# Membrane_Keypad.net
KiCad netlist of a schematic drawn in Altium Designer
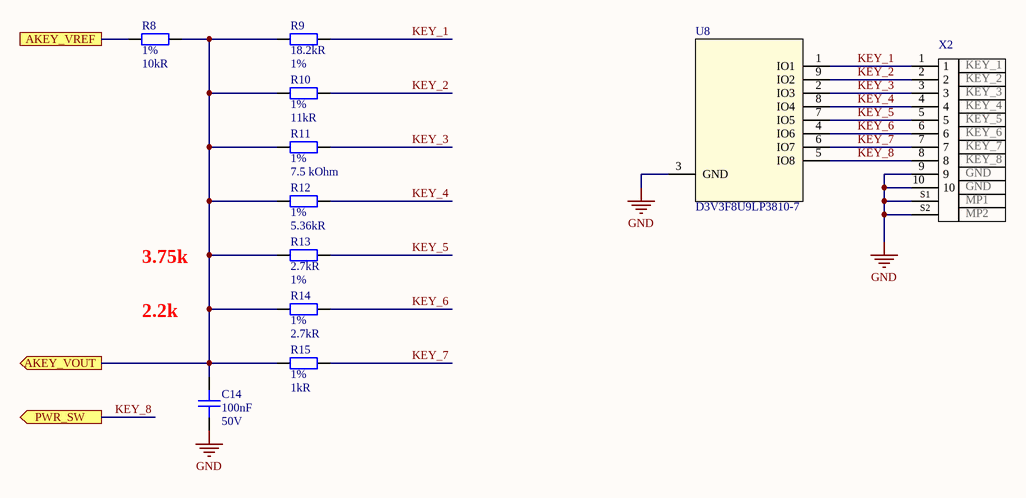
[diagram p0: Membrane_Keypad.SchDoc]

(export (version "E")
  (design (tool "Eeschema 10.0.6"))
  (components
    (comp (ref "C14")
      (value "CAP CER 0.1UF 50V X7R 0402")
      (footprint "C0402")
      (description "0.1µF ±10% 50V Ceramic Capacitor X7R 0402 (1005 Metric)")
      (fields
        (field (name "MANUFACTURER") "TDK")
        (field (name "MANUFACTURER PART NUMBER") "CGA2B3X7R1H104K050BB")
        (field (name "CAPACITANCE") "100nF")
        (field (name "VOLTAGE") "50V")
      )
      (libsource (lib "capacitors_smd") (part "CAP CER 0.1UF 50V X7R 0402"))
    )
    (comp (ref "R8")
      (value "RES SMD 10K OHM 1% 1/16W 0402")
      (footprint "0402R")
      (description "10 kOhms ±1% 0.063W, 1/16W Chip Resistor 0402 (1005 Metric) Moisture Resistant Thick Film")
      (fields
        (field (name "MANUFACTURER") "Yageo")
        (field (name "MANUFACTURER PART NUMBER") "RC0402FR-0710KP")
        (field (name "TOLERANCE") "1%")
        (field (name "RESISTANCE") "10kR")
      )
      (libsource (lib "resistors_smd") (part "RES SMD 10K OHM 1% 1/16W 0402"))
    )
    (comp (ref "R9")
      (value "RES SMD 18.2K OHM 1% 1/16W 0402")
      (footprint "R_0402")
      (description "18.2 kOhms ±1% 0.063W, 1/16W Chip Resistor 0402 (1005 Metric) Moisture Resistant Thick Film")
      (fields
        (field (name "MANUFACTURER") "Yageo")
        (field (name "MANUFACTURER PART NUMBER") "RC0402FR-0718K2L")
        (field (name "RESISTANCE") "18.2kR")
        (field (name "TOLERANCE") "1%")
      )
      (libsource (lib "resistors_smd") (part "RES SMD 18.2K OHM 1% 1/16W 0402"))
    )
    (comp (ref "R10")
      (value "RES SMD 11K OHM 1% 1/16W 0402")
      (footprint "R_0402")
      (description "11 kOhms ±1% 0.063W, 1/16W Chip Resistor 0402 (1005 Metric) Moisture Resistant Thick Film")
      (fields
        (field (name "MANUFACTURER") "Yageo")
        (field (name "MANUFACTURER PART NUMBER") "RC0402FR-0711KL")
        (field (name "TOLERANCE") "1%")
        (field (name "RESISTANCE") "11kR")
      )
      (libsource (lib "resistors_smd") (part "RES SMD 11K OHM 1% 1/16W 0402"))
    )
    (comp (ref "R11")
      (value "RES SMD 7.5K OHM 1% 1/10W 0603")
      (footprint "R_0402")
      (description "7.5 kOhms ±1% 0.1W, 1/10W Chip Resistor 0603 (1608 Metric) Moisture Resistant Thick Film")
      (fields
        (field (name "MANUFACTURER") "Yageo")
        (field (name "MANUFACTURER PART NUMBER") "RC0603FR-077K5L")
        (field (name "TOLERANCE") "1%")
        (field (name "RESISTANCE") "7.5 kOhm")
      )
      (libsource (lib "resistors_smd") (part "RES SMD 7.5K OHM 1% 1/10W 0603"))
    )
    (comp (ref "R12")
      (value "RES SMD 5.36K OHM 1% 1/16W 0402")
      (footprint "R_0402")
      (description "5.36 kOhms ±1% 0.063W, 1/16W Chip Resistor 0402 (1005 Metric) Moisture Resistant Thick Film")
      (fields
        (field (name "MANUFACTURER") "Yageo")
        (field (name "MANUFACTURER PART NUMBER") "RC0402FR-075K36L")
        (field (name "TOLERANCE") "1%")
        (field (name "RESISTANCE") "5.36kR")
      )
      (libsource (lib "resistors_smd") (part "RES SMD 5.36K OHM 1% 1/16W 0402"))
    )
    (comp (ref "R13")
      (value "RC0402FR-072K7L")
      (footprint "R_0402")
      (description "2.7 kOhms ±1% 0.063W, 1/16W Chip Resistor 0402 (1005 Metric) Moisture Resistant Thick Film")
      (fields
        (field (name "MANUFACTURER") "Yageo")
        (field (name "RESISTANCE") "2.7kR")
        (field (name "TOLERANCE") "1%")
      )
      (libsource (lib "resistors_smd") (part "RES SMD 2.7K OHM 1% 1/16W 0402"))
    )
    (comp (ref "R14")
      (value "RES SMD 2.7K OHM 1% 1/16W 0402")
      (footprint "R_0402")
      (description "2.7 kOhms ±1% 0.063W, 1/16W Chip Resistor 0402 (1005 Metric) Moisture Resistant Thick Film")
      (fields
        (field (name "MANUFACTURER") "Yageo")
        (field (name "MANUFACTURER PART NUMBER") "RC0402FR-072K7L")
        (field (name "TOLERANCE") "1%")
        (field (name "RESISTANCE") "2.7kR")
      )
      (libsource (lib "resistors_smd") (part "RES SMD 2.7K OHM 1% 1/16W 0402"))
    )
    (comp (ref "R15")
      (value "RES SMD 1K OHM 1% 1/16W 0402")
      (footprint "R_0402")
      (description "1 kOhms ±1% 0.063W, 1/16W Chip Resistor 0402 (1005 Metric) Moisture Resistant Thick Film")
      (fields
        (field (name "MANUFACTURER") "Yageo")
        (field (name "MANUFACTURER PART NUMBER") "RC0402FR-071KL")
        (field (name "TOLERANCE") "1%")
        (field (name "RESISTANCE") "1kR")
      )
      (libsource (lib "resistors_smd") (part "RES SMD 1K OHM 1% 1/16W 0402"))
    )
    (comp (ref "U8")
      (value "D3V3F8U9LP3810-7")
      (footprint "U-DFN3810-9")
      (description "5V (Typ) Clamp 5A (8/20µs) Ipp Tvs Diode Surface Mount U-DFN3810-9")
      (fields (field (name "MANUFACTURER") "Diodes"))
      (libsource (lib "diodes_tvs") (part "TVS DIODE PP U-DFN3810-9"))
    )
    (comp (ref "X2")
      (value "CONN 5034801000 FFC FPC 10POS 0.50MM R/A")
      (footprint "MOLEX_5034801000")
      (fields
        (field (name "PIN_7") "KEY_7")
        (field (name "PIN_1") "KEY_1")
        (field (name "PIN_2") "KEY_2")
        (field (name "PIN_3") "KEY_3")
        (field (name "PIN_4") "KEY_4")
        (field (name "PIN_5") "KEY_5")
        (field (name "PIN_6") "KEY_6")
        (field (name "PIN_8") "KEY_8")
        (field (name "MANUFACTURER") "Molex")
        (field (name "MANUFACTURER PART NUMBER") "503480-1000")
        (field (name "PIN_MP2") "MP2")
        (field (name "PIN_MP1") "MP1")
        (field (name "PIN_9") "GND")
        (field (name "PIN_10") "GND")
      )
      (libsource (lib "connectors_ffc") (part "CONN 5034801000 FFC FPC 10POS 0.50MM R/A"))
    )
  )
  (nets
    (net (code "1") (name "/AKEY_VOUT") (class "Default")
      (node (ref "C14") (pin "2") (pinfunction "2_2") (pintype "passive"))
      (node (ref "R10") (pin "1") (pinfunction "1_1") (pintype "passive"))
      (node (ref "R11") (pin "1") (pinfunction "1_1") (pintype "passive"))
      (node (ref "R12") (pin "1") (pinfunction "1_1") (pintype "passive"))
      (node (ref "R13") (pin "1") (pinfunction "1_1") (pintype "passive"))
      (node (ref "R14") (pin "1") (pinfunction "1_1") (pintype "passive"))
      (node (ref "R15") (pin "1") (pinfunction "1_1") (pintype "passive"))
      (node (ref "R8") (pin "1") (pinfunction "1_1") (pintype "passive"))
      (node (ref "R9") (pin "1") (pinfunction "1_1") (pintype "passive"))
    )
    (net (code "2") (name "/AKEY_VREF") (class "Default")
      (node (ref "R8") (pin "2") (pinfunction "2_2") (pintype "passive"))
    )
    (net (code "3") (name "/KEY_1") (class "Default")
      (node (ref "R9") (pin "2") (pinfunction "2_2") (pintype "passive"))
      (node (ref "U8") (pin "1") (pinfunction "IO1_1") (pintype "passive"))
      (node (ref "X2") (pin "1") (pinfunction "1_1") (pintype "passive"))
    )
    (net (code "4") (name "/KEY_2") (class "Default")
      (node (ref "R10") (pin "2") (pinfunction "2_2") (pintype "passive"))
      (node (ref "U8") (pin "9") (pinfunction "IO2_9") (pintype "passive"))
      (node (ref "X2") (pin "2") (pinfunction "2_2") (pintype "passive"))
    )
    (net (code "5") (name "/KEY_3") (class "Default")
      (node (ref "R11") (pin "2") (pinfunction "2_2") (pintype "passive"))
      (node (ref "U8") (pin "2") (pinfunction "IO3_2") (pintype "passive"))
      (node (ref "X2") (pin "3") (pinfunction "3_3") (pintype "passive"))
    )
    (net (code "6") (name "/KEY_4") (class "Default")
      (node (ref "R12") (pin "2") (pinfunction "2_2") (pintype "passive"))
      (node (ref "U8") (pin "8") (pinfunction "IO4_8") (pintype "passive"))
      (node (ref "X2") (pin "4") (pinfunction "4_4") (pintype "passive"))
    )
    (net (code "7") (name "/KEY_5") (class "Default")
      (node (ref "R13") (pin "2") (pinfunction "2_2") (pintype "passive"))
      (node (ref "U8") (pin "7") (pinfunction "IO5_7") (pintype "passive"))
      (node (ref "X2") (pin "5") (pinfunction "5_5") (pintype "passive"))
    )
    (net (code "8") (name "/KEY_6") (class "Default")
      (node (ref "R14") (pin "2") (pinfunction "2_2") (pintype "passive"))
      (node (ref "U8") (pin "4") (pinfunction "IO6_4") (pintype "passive"))
      (node (ref "X2") (pin "6") (pinfunction "6_6") (pintype "passive"))
    )
    (net (code "9") (name "/KEY_7") (class "Default")
      (node (ref "R15") (pin "2") (pinfunction "2_2") (pintype "passive"))
      (node (ref "U8") (pin "6") (pinfunction "IO7_6") (pintype "passive"))
      (node (ref "X2") (pin "7") (pinfunction "7_7") (pintype "passive"))
    )
    (net (code "10") (name "/KEY_8") (class "Default")
      (node (ref "U8") (pin "5") (pinfunction "IO8_5") (pintype "passive"))
      (node (ref "X2") (pin "8") (pinfunction "8_8") (pintype "passive"))
    )
    (net (code "11") (name "GND") (class "Default")
      (node (ref "C14") (pin "1") (pinfunction "1_1") (pintype "passive"))
      (node (ref "U8") (pin "3") (pinfunction "GND_3") (pintype "power_in"))
      (node (ref "X2") (pin "10") (pinfunction "10_10") (pintype "passive"))
      (node (ref "X2") (pin "9") (pinfunction "9_9") (pintype "passive"))
      (node (ref "X2") (pin "S1") (pinfunction "MP1_S1") (pintype "passive"))
      (node (ref "X2") (pin "S2") (pinfunction "MP2_S2") (pintype "passive"))
    )
  )
)
